# moduleduino.net
KiCad netlist of a schematic drawn in EAGLE
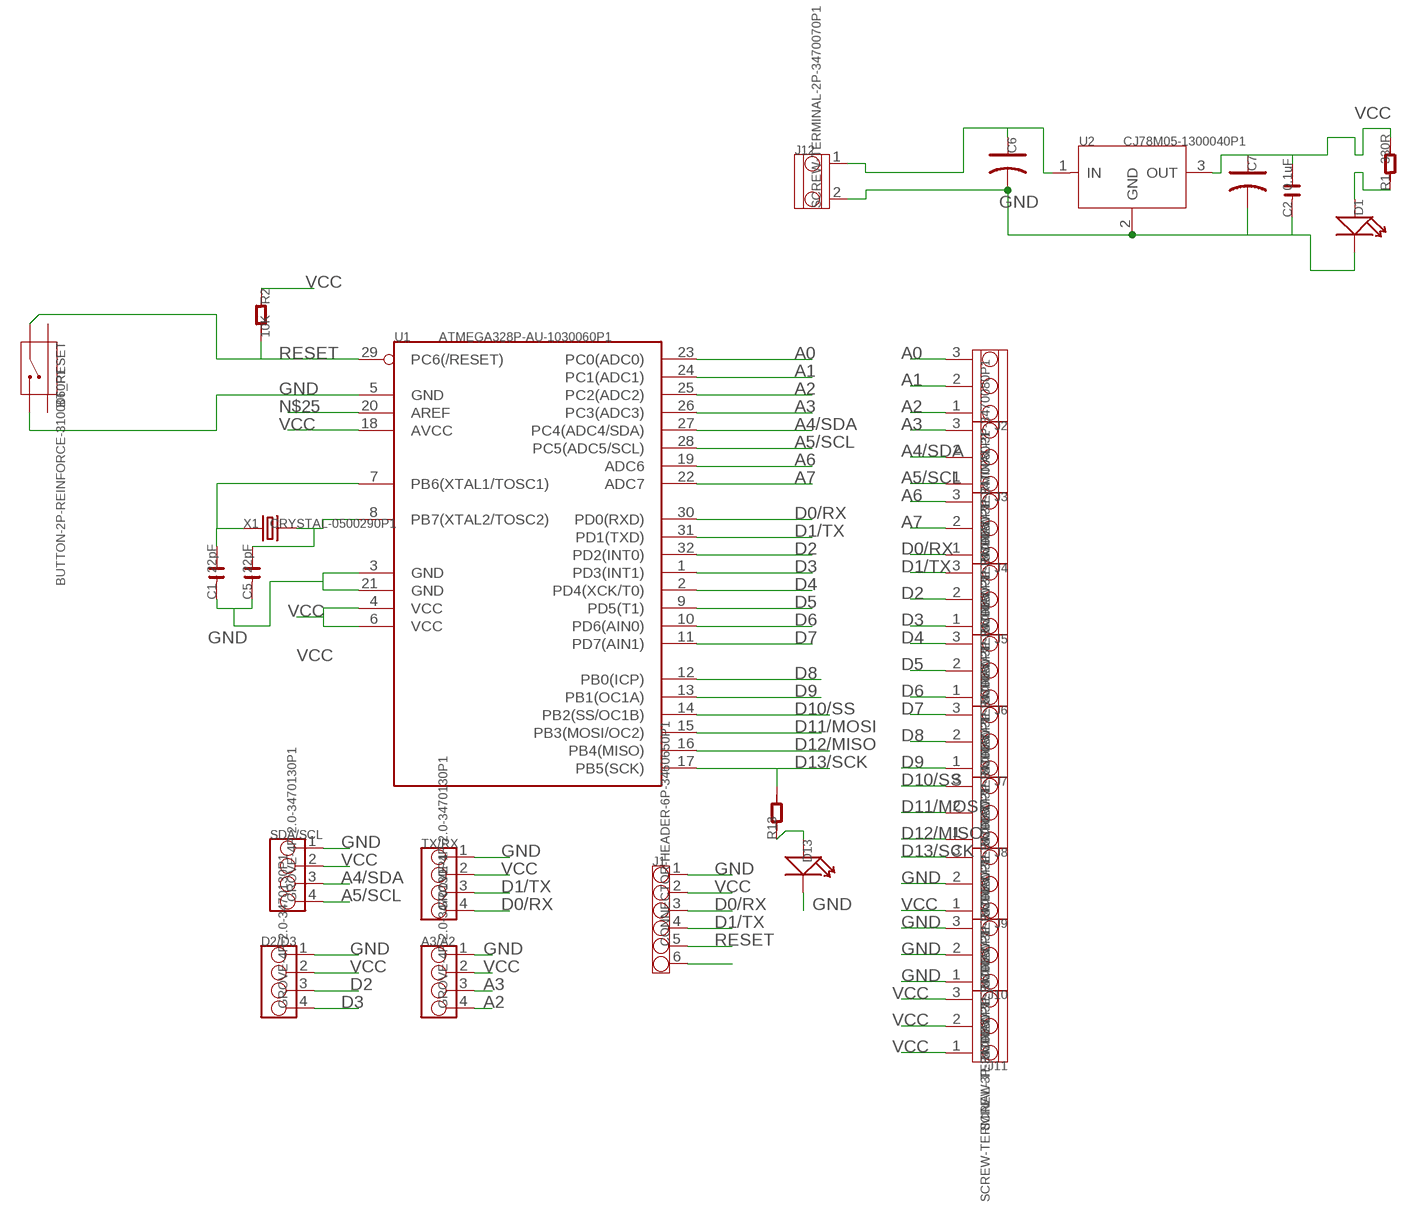
[diagram p0: schematic, sheet 1]

(export (version "E")
  (design (tool "Eeschema 10.0.6"))
  (components
    (comp (ref "A3/A2")
      (value "GROVE-4P-2.0-3470130P1")
      (footprint "eagle-import:4P-2.0")
      (libsource (lib "eagle-import") (part "GROVE-4P-2.0-3470130P1"))
    )
    (comp (ref "BT_RESET")
      (value "BUTTON-2P-REINFORCE-3100060P1")
      (footprint "eagle-import:4P-SMD-7.0X3.5X3.5H-90D")
      (libsource (lib "eagle-import") (part "BUTTON-2P-REINFORCE-3100060P1"))
    )
    (comp (ref "C1")
      (value "22pF")
      (footprint "eagle-import:C0603")
      (libsource (lib "eagle-import") (part "C-0603"))
    )
    (comp (ref "C2")
      (value "0.1uF")
      (footprint "eagle-import:C0603")
      (libsource (lib "eagle-import") (part "C-0603"))
    )
    (comp (ref "C5")
      (value "22pF")
      (footprint "eagle-import:C0603")
      (libsource (lib "eagle-import") (part "C-0603"))
    )
    (comp (ref "C6")
      (value "C-POLAR-B")
      (footprint "eagle-import:AVX-B")
      (libsource (lib "eagle-import") (part "C-POLAR-B"))
    )
    (comp (ref "C7")
      (value "C-POLAR-B")
      (footprint "eagle-import:AVX-B")
      (libsource (lib "eagle-import") (part "C-POLAR-B"))
    )
    (comp (ref "D1")
      (value "LED")
      (footprint "eagle-import:LED0603")
      (libsource (lib "eagle-import") (part "LED"))
    )
    (comp (ref "D2/D3")
      (value "GROVE-4P-2.0-3470130P1")
      (footprint "eagle-import:4P-2.0")
      (libsource (lib "eagle-import") (part "GROVE-4P-2.0-3470130P1"))
    )
    (comp (ref "D13")
      (value "LED")
      (footprint "eagle-import:LED0603")
      (libsource (lib "eagle-import") (part "LED"))
    )
    (comp (ref "J1")
      (value "CONNECTOR-HEADER-6P-3460650P1")
      (footprint "eagle-import:1X6P-2.54-2.54-11.6-3.0-BLACK-MALE")
      (libsource (lib "eagle-import") (part "CONNECTOR-HEADER-6P-3460650P1"))
    )
    (comp (ref "J2")
      (value "SCREW-TERMINAL-3P-3470080P1")
      (footprint "eagle-import:3P-5.0")
      (libsource (lib "eagle-import") (part "SCREW-TERMINAL-3P-3470080P1"))
    )
    (comp (ref "J3")
      (value "SCREW-TERMINAL-3P-3470080P1")
      (footprint "eagle-import:3P-5.0")
      (libsource (lib "eagle-import") (part "SCREW-TERMINAL-3P-3470080P1"))
    )
    (comp (ref "J4")
      (value "SCREW-TERMINAL-3P-3470080P1")
      (footprint "eagle-import:3P-5.0")
      (libsource (lib "eagle-import") (part "SCREW-TERMINAL-3P-3470080P1"))
    )
    (comp (ref "J5")
      (value "SCREW-TERMINAL-3P-3470080P1")
      (footprint "eagle-import:3P-5.0")
      (libsource (lib "eagle-import") (part "SCREW-TERMINAL-3P-3470080P1"))
    )
    (comp (ref "J6")
      (value "SCREW-TERMINAL-3P-3470080P1")
      (footprint "eagle-import:3P-5.0")
      (libsource (lib "eagle-import") (part "SCREW-TERMINAL-3P-3470080P1"))
    )
    (comp (ref "J7")
      (value "SCREW-TERMINAL-3P-3470080P1")
      (footprint "eagle-import:3P-5.0")
      (libsource (lib "eagle-import") (part "SCREW-TERMINAL-3P-3470080P1"))
    )
    (comp (ref "J8")
      (value "SCREW-TERMINAL-3P-3470080P1")
      (footprint "eagle-import:3P-5.0")
      (libsource (lib "eagle-import") (part "SCREW-TERMINAL-3P-3470080P1"))
    )
    (comp (ref "J9")
      (value "SCREW-TERMINAL-3P-3470080P1")
      (footprint "eagle-import:3P-5.0")
      (libsource (lib "eagle-import") (part "SCREW-TERMINAL-3P-3470080P1"))
    )
    (comp (ref "J10")
      (value "SCREW-TERMINAL-3P-3470080P1")
      (footprint "eagle-import:3P-5.0")
      (libsource (lib "eagle-import") (part "SCREW-TERMINAL-3P-3470080P1"))
    )
    (comp (ref "J11")
      (value "SCREW-TERMINAL-3P-3470080P1")
      (footprint "eagle-import:3P-5.0")
      (libsource (lib "eagle-import") (part "SCREW-TERMINAL-3P-3470080P1"))
    )
    (comp (ref "J12")
      (value "SCREW-TERMINAL-2P-3470070P1")
      (footprint "eagle-import:2P-3.5")
      (libsource (lib "eagle-import") (part "SCREW-TERMINAL-2P-3470070P1"))
    )
    (comp (ref "R1")
      (value "330R")
      (footprint "eagle-import:R0603")
      (libsource (lib "eagle-import") (part "R-0603"))
    )
    (comp (ref "R2")
      (value "10K")
      (footprint "eagle-import:R0603")
      (libsource (lib "eagle-import") (part "R-0603"))
    )
    (comp (ref "R13")
      (value "R-0603")
      (footprint "eagle-import:R0603")
      (libsource (lib "eagle-import") (part "R-0603"))
    )
    (comp (ref "SDA/SCL")
      (value "GROVE-4P-2.0-3470130P1")
      (footprint "eagle-import:4P-2.0")
      (libsource (lib "eagle-import") (part "GROVE-4P-2.0-3470130P1"))
    )
    (comp (ref "TX/RX")
      (value "GROVE-4P-2.0-3470130P1")
      (footprint "eagle-import:4P-2.0")
      (libsource (lib "eagle-import") (part "GROVE-4P-2.0-3470130P1"))
    )
    (comp (ref "U1")
      (value "ATMEGA328P-AU-1030060P1")
      (footprint "eagle-import:TQFP32")
      (libsource (lib "eagle-import") (part "ATMEGA328P-AU-1030060P1"))
    )
    (comp (ref "U2")
      (value "CJ78M05-1300040P1")
      (footprint "eagle-import:TO252")
      (libsource (lib "eagle-import") (part "CJ78M05-1300040P1"))
    )
    (comp (ref "X1")
      (value "CRYSTAL-0500290P1")
      (footprint "eagle-import:2P-SMD-5.0X3.2")
      (libsource (lib "eagle-import") (part "CRYSTAL-0500290P1"))
    )
  )
  (nets
    (net (code "1") (name "/A0") (class "Default")
      (node (ref "J2") (pin "3") (pinfunction "P$3_3") (pintype "bidirectional"))
      (node (ref "U1") (pin "23") (pinfunction "PC0(ADC0)_23") (pintype "bidirectional"))
    )
    (net (code "2") (name "/A1") (class "Default")
      (node (ref "J2") (pin "2") (pinfunction "P$2_2") (pintype "bidirectional"))
      (node (ref "U1") (pin "24") (pinfunction "PC1(ADC1)_24") (pintype "bidirectional"))
    )
    (net (code "3") (name "/A2") (class "Default")
      (node (ref "A3/A2") (pin "4") (pinfunction "4_4") (pintype "bidirectional"))
      (node (ref "J2") (pin "1") (pinfunction "P$1_1") (pintype "bidirectional"))
      (node (ref "U1") (pin "25") (pinfunction "PC2(ADC2)_25") (pintype "bidirectional"))
    )
    (net (code "4") (name "/A3") (class "Default")
      (node (ref "A3/A2") (pin "3") (pinfunction "3_3") (pintype "bidirectional"))
      (node (ref "J3") (pin "3") (pinfunction "P$3_3") (pintype "bidirectional"))
      (node (ref "U1") (pin "26") (pinfunction "PC3(ADC3)_26") (pintype "bidirectional"))
    )
    (net (code "5") (name "/A4{slash}SDA") (class "Default")
      (node (ref "J3") (pin "2") (pinfunction "P$2_2") (pintype "bidirectional"))
      (node (ref "SDA/SCL") (pin "3") (pinfunction "3_3") (pintype "bidirectional"))
      (node (ref "U1") (pin "27") (pinfunction "PC4(ADC4/SDA)_27") (pintype "bidirectional"))
    )
    (net (code "6") (name "/A5{slash}SCL") (class "Default")
      (node (ref "J3") (pin "1") (pinfunction "P$1_1") (pintype "bidirectional"))
      (node (ref "SDA/SCL") (pin "4") (pinfunction "4_4") (pintype "bidirectional"))
      (node (ref "U1") (pin "28") (pinfunction "PC5(ADC5/SCL)_28") (pintype "bidirectional"))
    )
    (net (code "7") (name "/A6") (class "Default")
      (node (ref "J4") (pin "3") (pinfunction "P$3_3") (pintype "bidirectional"))
      (node (ref "U1") (pin "19") (pinfunction "ADC6_19") (pintype "bidirectional"))
    )
    (net (code "8") (name "/A7") (class "Default")
      (node (ref "J4") (pin "2") (pinfunction "P$2_2") (pintype "bidirectional"))
      (node (ref "U1") (pin "22") (pinfunction "ADC7_22") (pintype "bidirectional"))
    )
    (net (code "9") (name "/D0{slash}RX") (class "Default")
      (node (ref "J1") (pin "3") (pinfunction "3_3") (pintype "bidirectional"))
      (node (ref "J4") (pin "1") (pinfunction "P$1_1") (pintype "bidirectional"))
      (node (ref "TX/RX") (pin "4") (pinfunction "4_4") (pintype "bidirectional"))
      (node (ref "U1") (pin "30") (pinfunction "PD0(RXD)_30") (pintype "bidirectional"))
    )
    (net (code "10") (name "/D1{slash}TX") (class "Default")
      (node (ref "J1") (pin "4") (pinfunction "4_4") (pintype "bidirectional"))
      (node (ref "J5") (pin "3") (pinfunction "P$3_3") (pintype "bidirectional"))
      (node (ref "TX/RX") (pin "3") (pinfunction "3_3") (pintype "bidirectional"))
      (node (ref "U1") (pin "31") (pinfunction "PD1(TXD)_31") (pintype "bidirectional"))
    )
    (net (code "11") (name "/D2") (class "Default")
      (node (ref "D2/D3") (pin "3") (pinfunction "3_3") (pintype "bidirectional"))
      (node (ref "J5") (pin "2") (pinfunction "P$2_2") (pintype "bidirectional"))
      (node (ref "U1") (pin "32") (pinfunction "PD2(INT0)_32") (pintype "bidirectional"))
    )
    (net (code "12") (name "/D3") (class "Default")
      (node (ref "D2/D3") (pin "4") (pinfunction "4_4") (pintype "bidirectional"))
      (node (ref "J5") (pin "1") (pinfunction "P$1_1") (pintype "bidirectional"))
      (node (ref "U1") (pin "1") (pinfunction "PD3(INT1)_1") (pintype "bidirectional"))
    )
    (net (code "13") (name "/D4") (class "Default")
      (node (ref "J6") (pin "3") (pinfunction "P$3_3") (pintype "bidirectional"))
      (node (ref "U1") (pin "2") (pinfunction "PD4(XCK/T0)_2") (pintype "bidirectional"))
    )
    (net (code "14") (name "/D5") (class "Default")
      (node (ref "J6") (pin "2") (pinfunction "P$2_2") (pintype "bidirectional"))
      (node (ref "U1") (pin "9") (pinfunction "PD5(T1)_9") (pintype "bidirectional"))
    )
    (net (code "15") (name "/D6") (class "Default")
      (node (ref "J6") (pin "1") (pinfunction "P$1_1") (pintype "bidirectional"))
      (node (ref "U1") (pin "10") (pinfunction "PD6(AIN0)_10") (pintype "bidirectional"))
    )
    (net (code "16") (name "/D7") (class "Default")
      (node (ref "J7") (pin "3") (pinfunction "P$3_3") (pintype "bidirectional"))
      (node (ref "U1") (pin "11") (pinfunction "PD7(AIN1)_11") (pintype "bidirectional"))
    )
    (net (code "17") (name "/D8") (class "Default")
      (node (ref "J7") (pin "2") (pinfunction "P$2_2") (pintype "bidirectional"))
      (node (ref "U1") (pin "12") (pinfunction "PB0(ICP)_12") (pintype "bidirectional"))
    )
    (net (code "18") (name "/D9") (class "Default")
      (node (ref "J7") (pin "1") (pinfunction "P$1_1") (pintype "bidirectional"))
      (node (ref "U1") (pin "13") (pinfunction "PB1(OC1A)_13") (pintype "bidirectional"))
    )
    (net (code "19") (name "/D10{slash}SS") (class "Default")
      (node (ref "J8") (pin "3") (pinfunction "P$3_3") (pintype "bidirectional"))
      (node (ref "U1") (pin "14") (pinfunction "PB2(SS/OC1B)_14") (pintype "bidirectional"))
    )
    (net (code "20") (name "/D11{slash}MOSI") (class "Default")
      (node (ref "J8") (pin "2") (pinfunction "P$2_2") (pintype "bidirectional"))
      (node (ref "U1") (pin "15") (pinfunction "PB3(MOSI/OC2)_15") (pintype "bidirectional"))
    )
    (net (code "21") (name "/D12{slash}MISO") (class "Default")
      (node (ref "J8") (pin "1") (pinfunction "P$1_1") (pintype "bidirectional"))
      (node (ref "U1") (pin "16") (pinfunction "PB4(MISO)_16") (pintype "bidirectional"))
    )
    (net (code "22") (name "/D13{slash}SCK") (class "Default")
      (node (ref "J9") (pin "3") (pinfunction "P$3_3") (pintype "bidirectional"))
      (node (ref "R13") (pin "2") (pinfunction "2_2") (pintype "bidirectional"))
      (node (ref "U1") (pin "17") (pinfunction "PB5(SCK)_17") (pintype "bidirectional"))
    )
    (net (code "23") (name "/GND") (class "Default")
      (node (ref "A3/A2") (pin "1") (pinfunction "1_1") (pintype "bidirectional"))
      (node (ref "BT_RESET") (pin "2") (pinfunction "2_2") (pintype "bidirectional"))
      (node (ref "C1") (pin "1") (pinfunction "1_1") (pintype "bidirectional"))
      (node (ref "C2") (pin "1") (pinfunction "1_1") (pintype "bidirectional"))
      (node (ref "C5") (pin "1") (pinfunction "1_1") (pintype "bidirectional"))
      (node (ref "C6") (pin "-") (pinfunction "2_-") (pintype "bidirectional"))
      (node (ref "C7") (pin "-") (pinfunction "2_-") (pintype "bidirectional"))
      (node (ref "D1") (pin "-") (pinfunction "-_-") (pintype "passive"))
      (node (ref "D13") (pin "-") (pinfunction "-_-") (pintype "passive"))
      (node (ref "D2/D3") (pin "1") (pinfunction "1_1") (pintype "bidirectional"))
      (node (ref "J1") (pin "1") (pinfunction "1_1") (pintype "bidirectional"))
      (node (ref "J10") (pin "1") (pinfunction "P$1_1") (pintype "bidirectional"))
      (node (ref "J10") (pin "2") (pinfunction "P$2_2") (pintype "bidirectional"))
      (node (ref "J10") (pin "3") (pinfunction "P$3_3") (pintype "bidirectional"))
      (node (ref "J12") (pin "2") (pinfunction "2_2") (pintype "bidirectional"))
      (node (ref "J9") (pin "2") (pinfunction "P$2_2") (pintype "bidirectional"))
      (node (ref "SDA/SCL") (pin "1") (pinfunction "1_1") (pintype "bidirectional"))
      (node (ref "TX/RX") (pin "1") (pinfunction "1_1") (pintype "bidirectional"))
      (node (ref "U1") (pin "21") (pinfunction "GND_21") (pintype "bidirectional"))
      (node (ref "U1") (pin "3") (pinfunction "GND_3") (pintype "bidirectional"))
      (node (ref "U1") (pin "5") (pinfunction "GND_5") (pintype "bidirectional"))
      (node (ref "U2") (pin "2") (pinfunction "GND_2") (pintype "bidirectional"))
    )
    (net (code "24") (name "/N$25") (class "Default")
      (node (ref "U1") (pin "20") (pinfunction "AREF_20") (pintype "bidirectional"))
    )
    (net (code "25") (name "/RESET") (class "Default")
      (node (ref "BT_RESET") (pin "1") (pinfunction "1_1") (pintype "bidirectional"))
      (node (ref "J1") (pin "5") (pinfunction "5_5") (pintype "bidirectional"))
      (node (ref "R2") (pin "2") (pinfunction "2_2") (pintype "bidirectional"))
      (node (ref "U1") (pin "29") (pinfunction "PC6(/RESET)_29") (pintype "bidirectional"))
    )
    (net (code "26") (name "/VCC") (class "Default")
      (node (ref "A3/A2") (pin "2") (pinfunction "2_2") (pintype "bidirectional"))
      (node (ref "C2") (pin "2") (pinfunction "2_2") (pintype "bidirectional"))
      (node (ref "C7") (pin "+") (pinfunction "1_+") (pintype "bidirectional"))
      (node (ref "D2/D3") (pin "2") (pinfunction "2_2") (pintype "bidirectional"))
      (node (ref "J1") (pin "2") (pinfunction "2_2") (pintype "bidirectional"))
      (node (ref "J11") (pin "1") (pinfunction "P$1_1") (pintype "bidirectional"))
      (node (ref "J11") (pin "2") (pinfunction "P$2_2") (pintype "bidirectional"))
      (node (ref "J11") (pin "3") (pinfunction "P$3_3") (pintype "bidirectional"))
      (node (ref "J9") (pin "1") (pinfunction "P$1_1") (pintype "bidirectional"))
      (node (ref "R1") (pin "2") (pinfunction "2_2") (pintype "bidirectional"))
      (node (ref "R2") (pin "1") (pinfunction "1_1") (pintype "bidirectional"))
      (node (ref "SDA/SCL") (pin "2") (pinfunction "2_2") (pintype "bidirectional"))
      (node (ref "TX/RX") (pin "2") (pinfunction "2_2") (pintype "bidirectional"))
      (node (ref "U1") (pin "18") (pinfunction "AVCC_18") (pintype "bidirectional"))
      (node (ref "U1") (pin "4") (pinfunction "VCC_4") (pintype "bidirectional"))
      (node (ref "U1") (pin "6") (pinfunction "VCC_6") (pintype "bidirectional"))
      (node (ref "U2") (pin "3") (pinfunction "OUT_3") (pintype "bidirectional"))
    )
    (net (code "27") (name "Net-(C6-1)") (class "Default")
      (node (ref "C6") (pin "+") (pinfunction "1_+") (pintype "bidirectional"))
      (node (ref "J12") (pin "1") (pinfunction "1_1") (pintype "bidirectional"))
      (node (ref "U2") (pin "1") (pinfunction "IN_1") (pintype "bidirectional"))
    )
    (net (code "28") (name "Net-(D1-Pad+)") (class "Default")
      (node (ref "D1") (pin "+") (pinfunction "+_+") (pintype "passive"))
      (node (ref "R1") (pin "1") (pinfunction "1_1") (pintype "bidirectional"))
    )
    (net (code "29") (name "Net-(D13-Pad+)") (class "Default")
      (node (ref "D13") (pin "+") (pinfunction "+_+") (pintype "passive"))
      (node (ref "R13") (pin "1") (pinfunction "1_1") (pintype "bidirectional"))
    )
    (net (code "30") (name "Net-(U1-PB6(XTAL1{slash}TOSC1))") (class "Default")
      (node (ref "C1") (pin "2") (pinfunction "2_2") (pintype "bidirectional"))
      (node (ref "U1") (pin "7") (pinfunction "PB6(XTAL1/TOSC1)_7") (pintype "bidirectional"))
      (node (ref "X1") (pin "1") (pinfunction "1_1") (pintype "passive"))
    )
    (net (code "31") (name "Net-(U1-PB7(XTAL2{slash}TOSC2))") (class "Default")
      (node (ref "C5") (pin "2") (pinfunction "2_2") (pintype "bidirectional"))
      (node (ref "U1") (pin "8") (pinfunction "PB7(XTAL2/TOSC2)_8") (pintype "bidirectional"))
      (node (ref "X1") (pin "2") (pinfunction "2_2") (pintype "passive"))
    )
    (net (code "32") (name "unconnected-(BT_RESET-PadS1)") (class "Default")
      (node (ref "BT_RESET") (pin "S1") (pinfunction "S1_S1") (pintype "bidirectional"))
    )
    (net (code "33") (name "unconnected-(BT_RESET-PadS2)") (class "Default")
      (node (ref "BT_RESET") (pin "S2") (pinfunction "S2_S2") (pintype "bidirectional"))
    )
    (net (code "34") (name "unconnected-(J1-Pad6)") (class "Default")
      (node (ref "J1") (pin "6") (pinfunction "6_6") (pintype "bidirectional"))
    )
  )
)
